# MAIN.net
KiCad netlist of a schematic drawn in Altium Designer
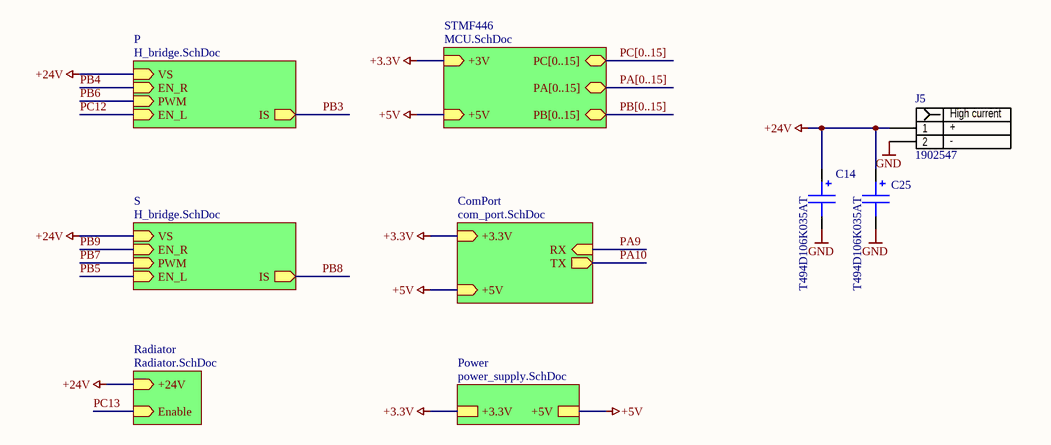
[diagram p0: MAIN.SchDoc]

(export (version "E")
  (design (tool "Eeschema 10.0.6"))
  (components
    (comp (ref "C14")
      (value "T494D106K035AT")
      (footprint "SamacSys:CAPPM7343X310N")
      (description "Capacitor Polarised")
      (fields (field (name "MOUSER PART NUMBER") "80-T494D106K035"))
      (libsource (lib "RobotLib") (part "T494D106K035AT"))
    )
    (comp (ref "C25")
      (value "T494D106K035AT")
      (footprint "SamacSys:CAPPM7343X310N")
      (description "Capacitor Polarised")
      (fields (field (name "MOUSER PART NUMBER") "80-T494D106K035"))
      (libsource (lib "RobotLib") (part "T494D106K035AT"))
    )
    (comp (ref "J5")
      (value "1902547")
      (footprint "1902547")
      (description "Connector")
      (fields (field (name "MOUSER PART NUMBER") "651-1902547"))
      (libsource (lib "RobotLib") (part "1902547"))
    )
  )
  (nets
    (net (code "40") (name "+24V") (class "Default")
      (node (ref "C14") (pin "1") (pinfunction "+_1") (pintype "passive"))
      (node (ref "C25") (pin "1") (pinfunction "+_1") (pintype "passive"))
      (node (ref "J5") (pin "1") (pinfunction "1_1") (pintype "passive"))
    )
    (net (code "55") (name "GND") (class "Default")
      (node (ref "C14") (pin "2") (pinfunction "-_2") (pintype "passive"))
      (node (ref "C25") (pin "2") (pinfunction "-_2") (pintype "passive"))
      (node (ref "J5") (pin "2") (pinfunction "2_2") (pintype "passive"))
    )
  )
)
